# hw-proto02.net
KiCad netlist of a schematic drawn in EAGLE
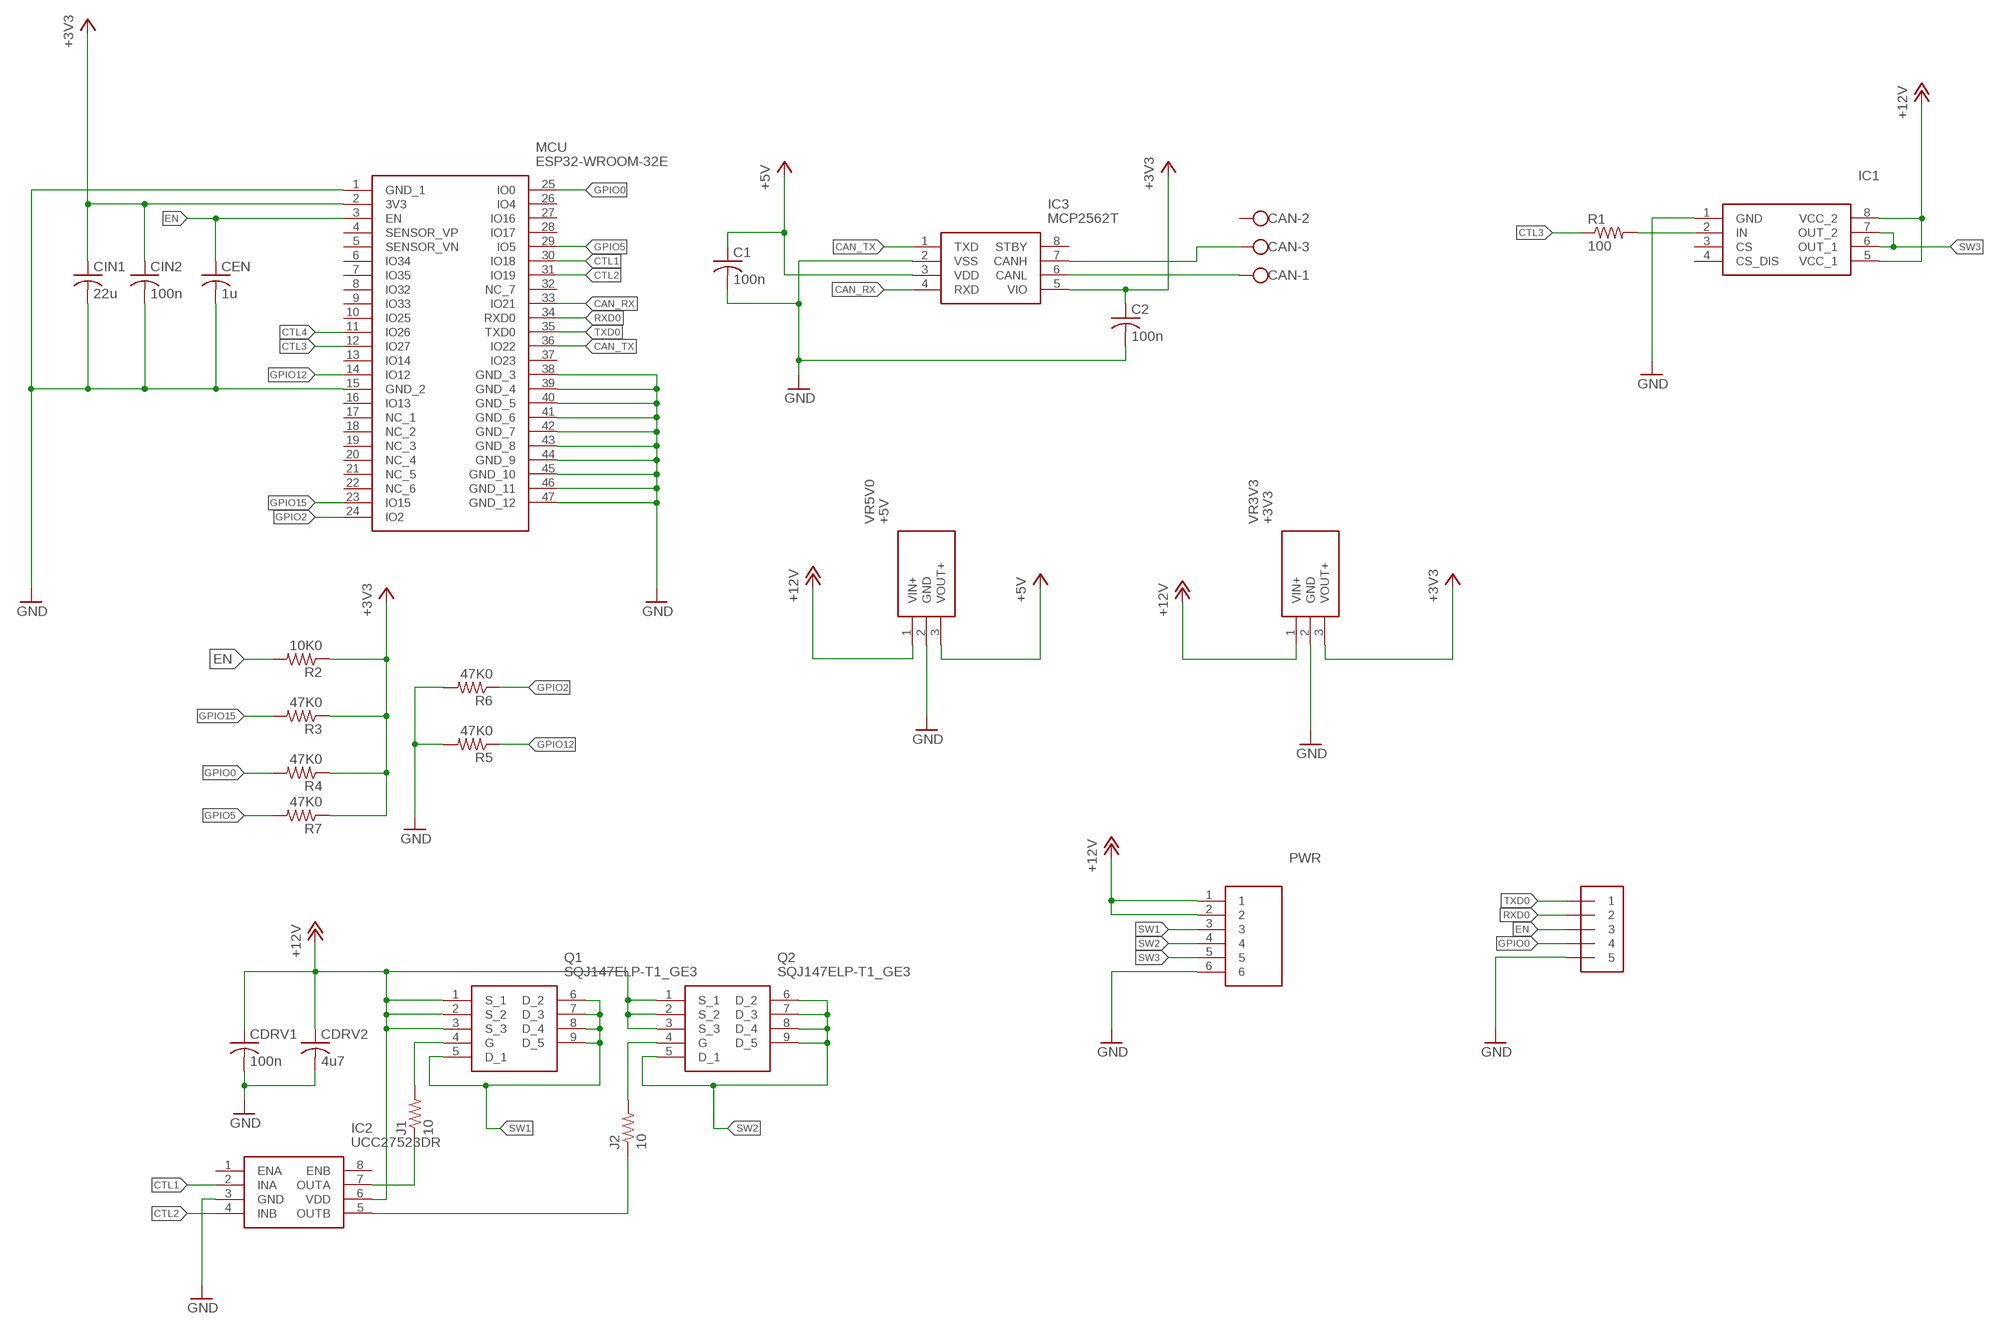
[diagram p0: schematic, sheet 1]

(export (version "E")
  (design (tool "Eeschema 10.0.6"))
  (components
    (comp (ref "C1")
      (value "100n")
      (footprint "eagle-import:C0603K")
      (libsource (lib "eagle-import") (part "C-USC0603K"))
    )
    (comp (ref "C2")
      (value "100n")
      (footprint "eagle-import:C0603K")
      (libsource (lib "eagle-import") (part "C-USC0603K"))
    )
    (comp (ref "CAN")
      (value "W237-103")
      (footprint "eagle-import:W237-103")
      (fields (field (name "MPN") "237-103"))
      (libsource (lib "eagle-import") (part "W237-103"))
    )
    (comp (ref "CDRV1")
      (value "100n")
      (footprint "eagle-import:C0603K")
      (libsource (lib "eagle-import") (part "C-USC0603K"))
    )
    (comp (ref "CDRV2")
      (value "4u7")
      (footprint "eagle-import:C0805K")
      (libsource (lib "eagle-import") (part "C-USC0805K"))
    )
    (comp (ref "CEN")
      (value "1u")
      (footprint "eagle-import:C0603K")
      (libsource (lib "eagle-import") (part "C-USC0603K"))
    )
    (comp (ref "CIN1")
      (value "22u")
      (footprint "eagle-import:C0805K")
      (libsource (lib "eagle-import") (part "C-USC0805K"))
    )
    (comp (ref "CIN2")
      (value "100n")
      (footprint "eagle-import:C0603K")
      (libsource (lib "eagle-import") (part "C-USC0603K"))
    )
    (comp (ref "IC1")
      (value "VN5E160MSTR-E")
      (footprint "eagle-import:SOIC127P600X175-8N")
      (fields (field (name "MOUSER_PART_NUMBER") "511-VN5E160MSTR-E"))
      (libsource (lib "eagle-import") (part "VN5E160MSTR-E"))
    )
    (comp (ref "IC2")
      (value "UCC27523DR")
      (footprint "eagle-import:SOIC127P600X175-8N")
      (fields (field (name "MOUSER_PART_NUMBER") "595-UCC27523DR"))
      (libsource (lib "eagle-import") (part "UCC27523DR"))
    )
    (comp (ref "IC3")
      (value "MCP2562T")
      (footprint "eagle-import:SOIC127P600X175-8N")
      (fields
        (field (name "MANUFACTURER_PART_NUMBER") "MCP2562T-H/SN")
        (field (name "MOUSER_PART_NUMBER") "579-MCP2562T-H/SN")
      )
      (libsource (lib "eagle-import") (part "MCP2562T-H_SN"))
    )
    (comp (ref "J1")
      (value "10")
      (footprint "eagle-import:0204_7")
      (libsource (lib "eagle-import") (part "R-US_0204/7"))
    )
    (comp (ref "J2")
      (value "10")
      (footprint "eagle-import:0204_7")
      (libsource (lib "eagle-import") (part "R-US_0204/7"))
    )
    (comp (ref "MCU")
      (value "ESP32-WROOM-32E")
      (footprint "eagle-import:ESP32WROOM32EN8R2")
      (fields
        (field (name "MANUFACTURER_PART_NUMBER") "ESP32-WROOM-32E-N8R2")
        (field (name "MOUSER_PART_NUMBER") "356-ESP32WRM32EN8R2")
      )
      (libsource (lib "eagle-import") (part "ESP32-WROOM-32E-N8R2"))
    )
    (comp (ref "PROG")
      (value "1X5")
      (footprint "eagle-import:1X05-3.5MM")
      (libsource (lib "eagle-import") (part "1X5"))
    )
    (comp (ref "PWR")
      (value "4DB-P108-06")
      (footprint "eagle-import:4DBP10806")
      (libsource (lib "eagle-import") (part "4DB-P108-06"))
    )
    (comp (ref "Q1")
      (value "SQJ147ELP-T1_GE3")
      (footprint "eagle-import:SQJ147ELPT1_GE3")
      (fields (field (name "MOUSER_PART_NUMBER") "78-SQJ147ELP-T1_GE3"))
      (libsource (lib "eagle-import") (part "SQJ147ELP-T1_GE3"))
    )
    (comp (ref "Q2")
      (value "SQJ147ELP-T1_GE3")
      (footprint "eagle-import:SQJ147ELPT1_GE3")
      (fields (field (name "MOUSER_PART_NUMBER") "78-SQJ147ELP-T1_GE3"))
      (libsource (lib "eagle-import") (part "SQJ147ELP-T1_GE3"))
    )
    (comp (ref "R1")
      (value "100")
      (footprint "eagle-import:0204_7")
      (libsource (lib "eagle-import") (part "R-US_0204/7"))
    )
    (comp (ref "R2")
      (value "10K0")
      (footprint "eagle-import:R0603")
      (libsource (lib "eagle-import") (part "R-US_R0603"))
    )
    (comp (ref "R3")
      (value "47K0")
      (footprint "eagle-import:R0603")
      (libsource (lib "eagle-import") (part "R-US_R0603"))
    )
    (comp (ref "R4")
      (value "47K0")
      (footprint "eagle-import:R0603")
      (libsource (lib "eagle-import") (part "R-US_R0603"))
    )
    (comp (ref "R5")
      (value "47K0")
      (footprint "eagle-import:R0603")
      (libsource (lib "eagle-import") (part "R-US_R0603"))
    )
    (comp (ref "R6")
      (value "47K0")
      (footprint "eagle-import:R0603")
      (libsource (lib "eagle-import") (part "R-US_R0603"))
    )
    (comp (ref "R7")
      (value "47K0")
      (footprint "eagle-import:R0603")
      (libsource (lib "eagle-import") (part "R-US_R0603"))
    )
    (comp (ref "VR3V3")
      (value "+3V3")
      (footprint "eagle-import:TSR-1-2433")
      (fields
        (field (name "MANUFACTURER_PART_NUMBER") "TSR 1-2433E")
        (field (name "MOUSER_PART_NUMBER") "495-TSR1-2433E")
      )
      (libsource (lib "eagle-import") (part "TSR_1-2433E"))
    )
    (comp (ref "VR5V0")
      (value "+5V")
      (footprint "eagle-import:TSR-1-2433")
      (fields
        (field (name "MANUFACTURER_PART_NUMBER") "TSR 1-2433E")
        (field (name "MOUSER_PART_NUMBER") "495-TSR1-2433E")
      )
      (libsource (lib "eagle-import") (part "TSR_1-2433E"))
    )
  )
  (nets
    (net (code "1") (name "+3V3") (class "Default")
      (node (ref "C2") (pin "1") (pinfunction "1_1") (pintype "passive"))
      (node (ref "CIN1") (pin "1") (pinfunction "1_1") (pintype "passive"))
      (node (ref "CIN2") (pin "1") (pinfunction "1_1") (pintype "passive"))
      (node (ref "IC3") (pin "5") (pinfunction "VIO_5") (pintype "bidirectional"))
      (node (ref "MCU") (pin "2") (pinfunction "3V3_2") (pintype "bidirectional"))
      (node (ref "R2") (pin "1") (pinfunction "1_1") (pintype "passive"))
      (node (ref "R3") (pin "1") (pinfunction "1_1") (pintype "passive"))
      (node (ref "R4") (pin "1") (pinfunction "1_1") (pintype "passive"))
      (node (ref "R7") (pin "1") (pinfunction "1_1") (pintype "passive"))
      (node (ref "VR3V3") (pin "3") (pinfunction "VOUT+_3") (pintype "output"))
    )
    (net (code "2") (name "+5V") (class "Default")
      (node (ref "C1") (pin "1") (pinfunction "1_1") (pintype "passive"))
      (node (ref "IC3") (pin "3") (pinfunction "VDD_3") (pintype "bidirectional"))
      (node (ref "VR5V0") (pin "3") (pinfunction "VOUT+_3") (pintype "output"))
    )
    (net (code "3") (name "+12V") (class "Default")
      (node (ref "CDRV1") (pin "1") (pinfunction "1_1") (pintype "passive"))
      (node (ref "CDRV2") (pin "1") (pinfunction "1_1") (pintype "passive"))
      (node (ref "IC1") (pin "5") (pinfunction "VCC_1_5") (pintype "bidirectional"))
      (node (ref "IC1") (pin "8") (pinfunction "VCC_2_8") (pintype "bidirectional"))
      (node (ref "IC2") (pin "6") (pinfunction "VDD_6") (pintype "bidirectional"))
      (node (ref "PWR") (pin "1") (pinfunction "1_1") (pintype "bidirectional"))
      (node (ref "PWR") (pin "2") (pinfunction "2_2") (pintype "bidirectional"))
      (node (ref "Q1") (pin "1") (pinfunction "S_1_1") (pintype "bidirectional"))
      (node (ref "Q1") (pin "2") (pinfunction "S_2_2") (pintype "bidirectional"))
      (node (ref "Q1") (pin "3") (pinfunction "S_3_3") (pintype "bidirectional"))
      (node (ref "Q2") (pin "1") (pinfunction "S_1_1") (pintype "bidirectional"))
      (node (ref "Q2") (pin "2") (pinfunction "S_2_2") (pintype "bidirectional"))
      (node (ref "Q2") (pin "3") (pinfunction "S_3_3") (pintype "bidirectional"))
      (node (ref "VR3V3") (pin "1") (pinfunction "VIN+_1") (pintype "input"))
      (node (ref "VR5V0") (pin "1") (pinfunction "VIN+_1") (pintype "input"))
    )
    (net (code "4") (name "CAN_RX") (class "Default")
      (node (ref "IC3") (pin "4") (pinfunction "RXD_4") (pintype "bidirectional"))
      (node (ref "MCU") (pin "33") (pinfunction "IO21_33") (pintype "bidirectional"))
    )
    (net (code "5") (name "CAN_TX") (class "Default")
      (node (ref "IC3") (pin "1") (pinfunction "TXD_1") (pintype "bidirectional"))
      (node (ref "MCU") (pin "36") (pinfunction "IO22_36") (pintype "bidirectional"))
    )
    (net (code "6") (name "CTL1") (class "Default")
      (node (ref "IC2") (pin "2") (pinfunction "INA_2") (pintype "bidirectional"))
      (node (ref "MCU") (pin "30") (pinfunction "IO18_30") (pintype "bidirectional"))
    )
    (net (code "7") (name "CTL2") (class "Default")
      (node (ref "IC2") (pin "4") (pinfunction "INB_4") (pintype "bidirectional"))
      (node (ref "MCU") (pin "31") (pinfunction "IO19_31") (pintype "bidirectional"))
    )
    (net (code "8") (name "CTL3") (class "Default")
      (node (ref "MCU") (pin "12") (pinfunction "IO27_12") (pintype "bidirectional"))
      (node (ref "R1") (pin "1") (pinfunction "1_1") (pintype "passive"))
    )
    (net (code "9") (name "CTL4") (class "Default")
      (node (ref "MCU") (pin "11") (pinfunction "IO26_11") (pintype "bidirectional"))
    )
    (net (code "10") (name "EN") (class "Default")
      (node (ref "CEN") (pin "1") (pinfunction "1_1") (pintype "passive"))
      (node (ref "MCU") (pin "3") (pinfunction "EN_3") (pintype "bidirectional"))
      (node (ref "PROG") (pin "3") (pinfunction "3_3") (pintype "passive"))
      (node (ref "R2") (pin "2") (pinfunction "2_2") (pintype "passive"))
    )
    (net (code "11") (name "GND") (class "Default")
      (node (ref "C1") (pin "2") (pinfunction "2_2") (pintype "passive"))
      (node (ref "C2") (pin "2") (pinfunction "2_2") (pintype "passive"))
      (node (ref "CDRV1") (pin "2") (pinfunction "2_2") (pintype "passive"))
      (node (ref "CDRV2") (pin "2") (pinfunction "2_2") (pintype "passive"))
      (node (ref "CEN") (pin "2") (pinfunction "2_2") (pintype "passive"))
      (node (ref "CIN1") (pin "2") (pinfunction "2_2") (pintype "passive"))
      (node (ref "CIN2") (pin "2") (pinfunction "2_2") (pintype "passive"))
      (node (ref "IC1") (pin "1") (pinfunction "GND_1") (pintype "bidirectional"))
      (node (ref "IC2") (pin "3") (pinfunction "GND_3") (pintype "bidirectional"))
      (node (ref "IC3") (pin "2") (pinfunction "VSS_2") (pintype "bidirectional"))
      (node (ref "MCU") (pin "1") (pinfunction "GND_1_1") (pintype "bidirectional"))
      (node (ref "MCU") (pin "15") (pinfunction "GND_2_15") (pintype "bidirectional"))
      (node (ref "MCU") (pin "38") (pinfunction "GND_3_38") (pintype "bidirectional"))
      (node (ref "MCU") (pin "39") (pinfunction "GND_4_39") (pintype "bidirectional"))
      (node (ref "MCU") (pin "40") (pinfunction "GND_5_40") (pintype "bidirectional"))
      (node (ref "MCU") (pin "41") (pinfunction "GND_6_41") (pintype "bidirectional"))
      (node (ref "MCU") (pin "42") (pinfunction "GND_7_42") (pintype "bidirectional"))
      (node (ref "MCU") (pin "43") (pinfunction "GND_8_43") (pintype "bidirectional"))
      (node (ref "MCU") (pin "44") (pinfunction "GND_9_44") (pintype "bidirectional"))
      (node (ref "MCU") (pin "45") (pinfunction "GND_10_45") (pintype "bidirectional"))
      (node (ref "MCU") (pin "46") (pinfunction "GND_11_46") (pintype "bidirectional"))
      (node (ref "MCU") (pin "47") (pinfunction "GND_12_47") (pintype "bidirectional"))
      (node (ref "PROG") (pin "5") (pinfunction "5_5") (pintype "passive"))
      (node (ref "PWR") (pin "6") (pinfunction "6_6") (pintype "bidirectional"))
      (node (ref "R5") (pin "2") (pinfunction "2_2") (pintype "passive"))
      (node (ref "R6") (pin "2") (pinfunction "2_2") (pintype "passive"))
      (node (ref "VR3V3") (pin "2") (pinfunction "GND_2") (pintype "power_in"))
      (node (ref "VR5V0") (pin "2") (pinfunction "GND_2") (pintype "power_in"))
    )
    (net (code "12") (name "GPIO0") (class "Default")
      (node (ref "MCU") (pin "25") (pinfunction "IO0_25") (pintype "bidirectional"))
      (node (ref "PROG") (pin "4") (pinfunction "4_4") (pintype "passive"))
      (node (ref "R4") (pin "2") (pinfunction "2_2") (pintype "passive"))
    )
    (net (code "13") (name "GPIO2") (class "Default")
      (node (ref "MCU") (pin "24") (pinfunction "IO2_24") (pintype "bidirectional"))
      (node (ref "R6") (pin "1") (pinfunction "1_1") (pintype "passive"))
    )
    (net (code "14") (name "GPIO5") (class "Default")
      (node (ref "MCU") (pin "29") (pinfunction "IO5_29") (pintype "bidirectional"))
      (node (ref "R7") (pin "2") (pinfunction "2_2") (pintype "passive"))
    )
    (net (code "15") (name "GPIO12") (class "Default")
      (node (ref "MCU") (pin "14") (pinfunction "IO12_14") (pintype "bidirectional"))
      (node (ref "R5") (pin "1") (pinfunction "1_1") (pintype "passive"))
    )
    (net (code "16") (name "GPIO15") (class "Default")
      (node (ref "MCU") (pin "23") (pinfunction "IO15_23") (pintype "bidirectional"))
      (node (ref "R3") (pin "2") (pinfunction "2_2") (pintype "passive"))
    )
    (net (code "17") (name "Net-(CANA-KL)") (class "Default")
      (node (ref "CAN") (pin "1") (pinfunction "KL_1") (pintype "passive"))
      (node (ref "IC3") (pin "6") (pinfunction "CANL_6") (pintype "bidirectional"))
    )
    (net (code "18") (name "Net-(CANC-KL)") (class "Default")
      (node (ref "CAN") (pin "3") (pinfunction "KL_3") (pintype "passive"))
      (node (ref "IC3") (pin "7") (pinfunction "CANH_7") (pintype "bidirectional"))
    )
    (net (code "19") (name "Net-(IC1-IN)") (class "Default")
      (node (ref "IC1") (pin "2") (pinfunction "IN_2") (pintype "bidirectional"))
      (node (ref "R1") (pin "2") (pinfunction "2_2") (pintype "passive"))
    )
    (net (code "20") (name "Net-(IC2-OUTA)") (class "Default")
      (node (ref "IC2") (pin "7") (pinfunction "OUTA_7") (pintype "bidirectional"))
      (node (ref "J1") (pin "1") (pinfunction "1_1") (pintype "passive"))
    )
    (net (code "21") (name "Net-(IC2-OUTB)") (class "Default")
      (node (ref "IC2") (pin "5") (pinfunction "OUTB_5") (pintype "bidirectional"))
      (node (ref "J2") (pin "1") (pinfunction "1_1") (pintype "passive"))
    )
    (net (code "22") (name "Net-(Q1-G)") (class "Default")
      (node (ref "J1") (pin "2") (pinfunction "2_2") (pintype "passive"))
      (node (ref "Q1") (pin "4") (pinfunction "G_4") (pintype "bidirectional"))
    )
    (net (code "23") (name "Net-(Q2-G)") (class "Default")
      (node (ref "J2") (pin "2") (pinfunction "2_2") (pintype "passive"))
      (node (ref "Q2") (pin "4") (pinfunction "G_4") (pintype "bidirectional"))
    )
    (net (code "24") (name "RXD0") (class "Default")
      (node (ref "MCU") (pin "34") (pinfunction "RXD0_34") (pintype "bidirectional"))
      (node (ref "PROG") (pin "2") (pinfunction "2_2") (pintype "passive"))
    )
    (net (code "25") (name "SW1") (class "Default")
      (node (ref "PWR") (pin "3") (pinfunction "3_3") (pintype "bidirectional"))
      (node (ref "Q1") (pin "5") (pinfunction "D_1_5") (pintype "bidirectional"))
      (node (ref "Q1") (pin "6") (pinfunction "D_2_6") (pintype "bidirectional"))
      (node (ref "Q1") (pin "7") (pinfunction "D_3_7") (pintype "bidirectional"))
      (node (ref "Q1") (pin "8") (pinfunction "D_4_8") (pintype "bidirectional"))
      (node (ref "Q1") (pin "9") (pinfunction "D_5_9") (pintype "bidirectional"))
    )
    (net (code "26") (name "SW2") (class "Default")
      (node (ref "PWR") (pin "4") (pinfunction "4_4") (pintype "bidirectional"))
      (node (ref "Q2") (pin "5") (pinfunction "D_1_5") (pintype "bidirectional"))
      (node (ref "Q2") (pin "6") (pinfunction "D_2_6") (pintype "bidirectional"))
      (node (ref "Q2") (pin "7") (pinfunction "D_3_7") (pintype "bidirectional"))
      (node (ref "Q2") (pin "8") (pinfunction "D_4_8") (pintype "bidirectional"))
      (node (ref "Q2") (pin "9") (pinfunction "D_5_9") (pintype "bidirectional"))
    )
    (net (code "27") (name "SW3") (class "Default")
      (node (ref "IC1") (pin "6") (pinfunction "OUT_1_6") (pintype "bidirectional"))
      (node (ref "IC1") (pin "7") (pinfunction "OUT_2_7") (pintype "bidirectional"))
      (node (ref "PWR") (pin "5") (pinfunction "5_5") (pintype "bidirectional"))
    )
    (net (code "28") (name "TXD0") (class "Default")
      (node (ref "MCU") (pin "35") (pinfunction "TXD0_35") (pintype "bidirectional"))
      (node (ref "PROG") (pin "1") (pinfunction "1_1") (pintype "passive"))
    )
    (net (code "29") (name "unconnected-(CANB-KL-Pad2)") (class "Default")
      (node (ref "CAN") (pin "2") (pinfunction "KL_2") (pintype "passive"))
    )
    (net (code "30") (name "unconnected-(IC1-CS-Pad3)") (class "Default")
      (node (ref "IC1") (pin "3") (pinfunction "CS_3") (pintype "bidirectional"))
    )
    (net (code "31") (name "unconnected-(IC1-CS_DIS-Pad4)") (class "Default")
      (node (ref "IC1") (pin "4") (pinfunction "CS_DIS_4") (pintype "bidirectional"))
    )
    (net (code "32") (name "unconnected-(IC2-ENA-Pad1)") (class "Default")
      (node (ref "IC2") (pin "1") (pinfunction "ENA_1") (pintype "bidirectional"))
    )
    (net (code "33") (name "unconnected-(IC2-ENB-Pad8)") (class "Default")
      (node (ref "IC2") (pin "8") (pinfunction "ENB_8") (pintype "bidirectional"))
    )
    (net (code "34") (name "unconnected-(IC3-STBY-Pad8)") (class "Default")
      (node (ref "IC3") (pin "8") (pinfunction "STBY_8") (pintype "bidirectional"))
    )
    (net (code "35") (name "unconnected-(MCU-IO4-Pad26)") (class "Default")
      (node (ref "MCU") (pin "26") (pinfunction "IO4_26") (pintype "bidirectional"))
    )
    (net (code "36") (name "unconnected-(MCU-IO13-Pad16)") (class "Default")
      (node (ref "MCU") (pin "16") (pinfunction "IO13_16") (pintype "bidirectional"))
    )
    (net (code "37") (name "unconnected-(MCU-IO14-Pad13)") (class "Default")
      (node (ref "MCU") (pin "13") (pinfunction "IO14_13") (pintype "bidirectional"))
    )
    (net (code "38") (name "unconnected-(MCU-IO16-Pad27)") (class "Default")
      (node (ref "MCU") (pin "27") (pinfunction "IO16_27") (pintype "bidirectional"))
    )
    (net (code "39") (name "unconnected-(MCU-IO17-Pad28)") (class "Default")
      (node (ref "MCU") (pin "28") (pinfunction "IO17_28") (pintype "bidirectional"))
    )
    (net (code "40") (name "unconnected-(MCU-IO23-Pad37)") (class "Default")
      (node (ref "MCU") (pin "37") (pinfunction "IO23_37") (pintype "bidirectional"))
    )
    (net (code "41") (name "unconnected-(MCU-IO25-Pad10)") (class "Default")
      (node (ref "MCU") (pin "10") (pinfunction "IO25_10") (pintype "bidirectional"))
    )
    (net (code "42") (name "unconnected-(MCU-IO32-Pad8)") (class "Default")
      (node (ref "MCU") (pin "8") (pinfunction "IO32_8") (pintype "bidirectional"))
    )
    (net (code "43") (name "unconnected-(MCU-IO33-Pad9)") (class "Default")
      (node (ref "MCU") (pin "9") (pinfunction "IO33_9") (pintype "bidirectional"))
    )
    (net (code "44") (name "unconnected-(MCU-IO34-Pad6)") (class "Default")
      (node (ref "MCU") (pin "6") (pinfunction "IO34_6") (pintype "bidirectional"))
    )
    (net (code "45") (name "unconnected-(MCU-IO35-Pad7)") (class "Default")
      (node (ref "MCU") (pin "7") (pinfunction "IO35_7") (pintype "bidirectional"))
    )
    (net (code "46") (name "unconnected-(MCU-NC_1-Pad17)") (class "Default")
      (node (ref "MCU") (pin "17") (pinfunction "NC_1_17") (pintype "bidirectional"))
    )
    (net (code "47") (name "unconnected-(MCU-NC_2-Pad18)") (class "Default")
      (node (ref "MCU") (pin "18") (pinfunction "NC_2_18") (pintype "bidirectional"))
    )
    (net (code "48") (name "unconnected-(MCU-NC_3-Pad19)") (class "Default")
      (node (ref "MCU") (pin "19") (pinfunction "NC_3_19") (pintype "bidirectional"))
    )
    (net (code "49") (name "unconnected-(MCU-NC_4-Pad20)") (class "Default")
      (node (ref "MCU") (pin "20") (pinfunction "NC_4_20") (pintype "bidirectional"))
    )
    (net (code "50") (name "unconnected-(MCU-NC_5-Pad21)") (class "Default")
      (node (ref "MCU") (pin "21") (pinfunction "NC_5_21") (pintype "bidirectional"))
    )
    (net (code "51") (name "unconnected-(MCU-NC_6-Pad22)") (class "Default")
      (node (ref "MCU") (pin "22") (pinfunction "NC_6_22") (pintype "bidirectional"))
    )
    (net (code "52") (name "unconnected-(MCU-NC_7-Pad32)") (class "Default")
      (node (ref "MCU") (pin "32") (pinfunction "NC_7_32") (pintype "bidirectional"))
    )
    (net (code "53") (name "unconnected-(MCU-SENSOR_VN-Pad5)") (class "Default")
      (node (ref "MCU") (pin "5") (pinfunction "SENSOR_VN_5") (pintype "bidirectional"))
    )
    (net (code "54") (name "unconnected-(MCU-SENSOR_VP-Pad4)") (class "Default")
      (node (ref "MCU") (pin "4") (pinfunction "SENSOR_VP_4") (pintype "bidirectional"))
    )
  )
)
